# BoeBot-Schematic.net
KiCad netlist of a schematic drawn in EAGLE
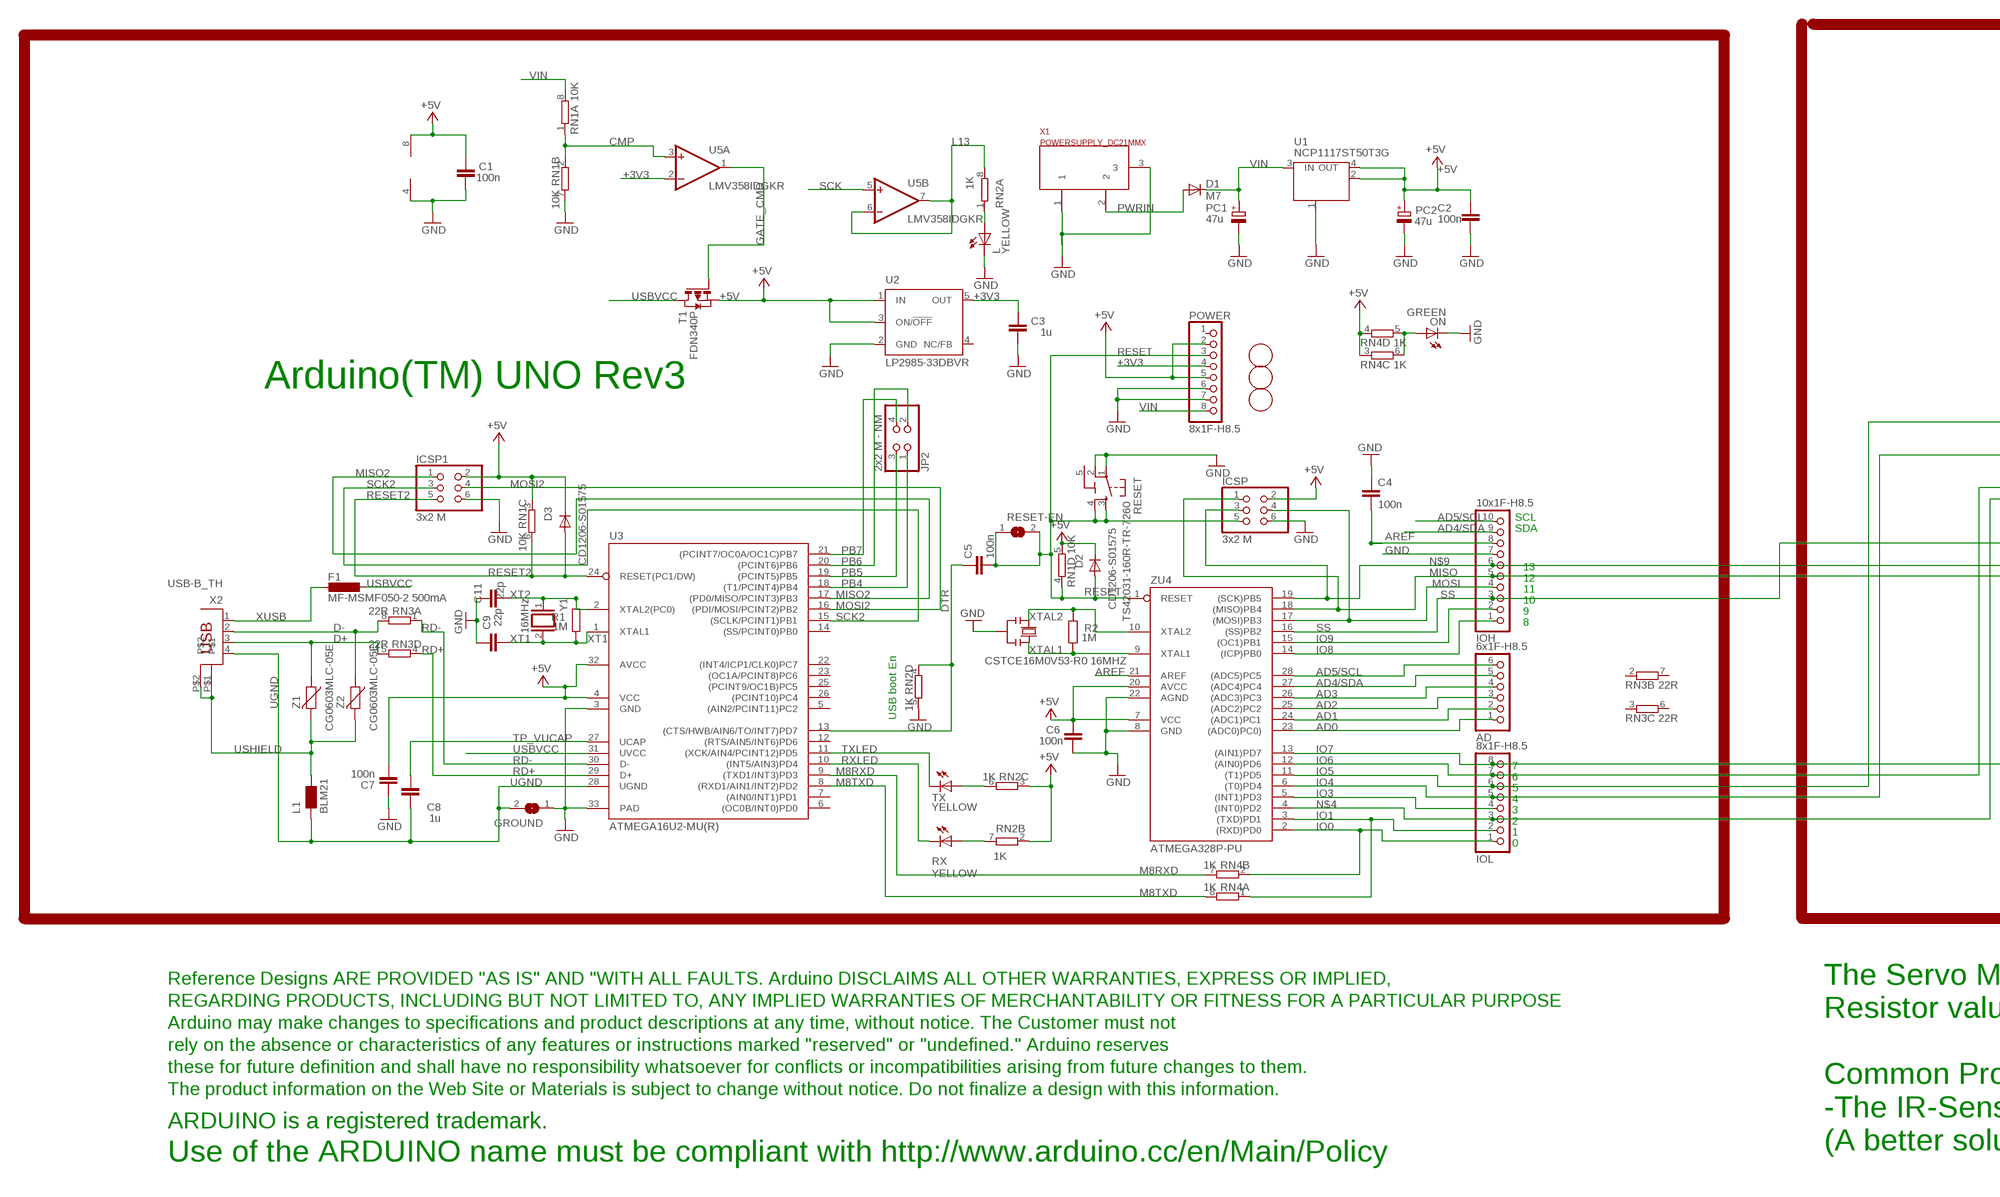
[diagram p0: schematic, sheet 1, part 1 of 2]
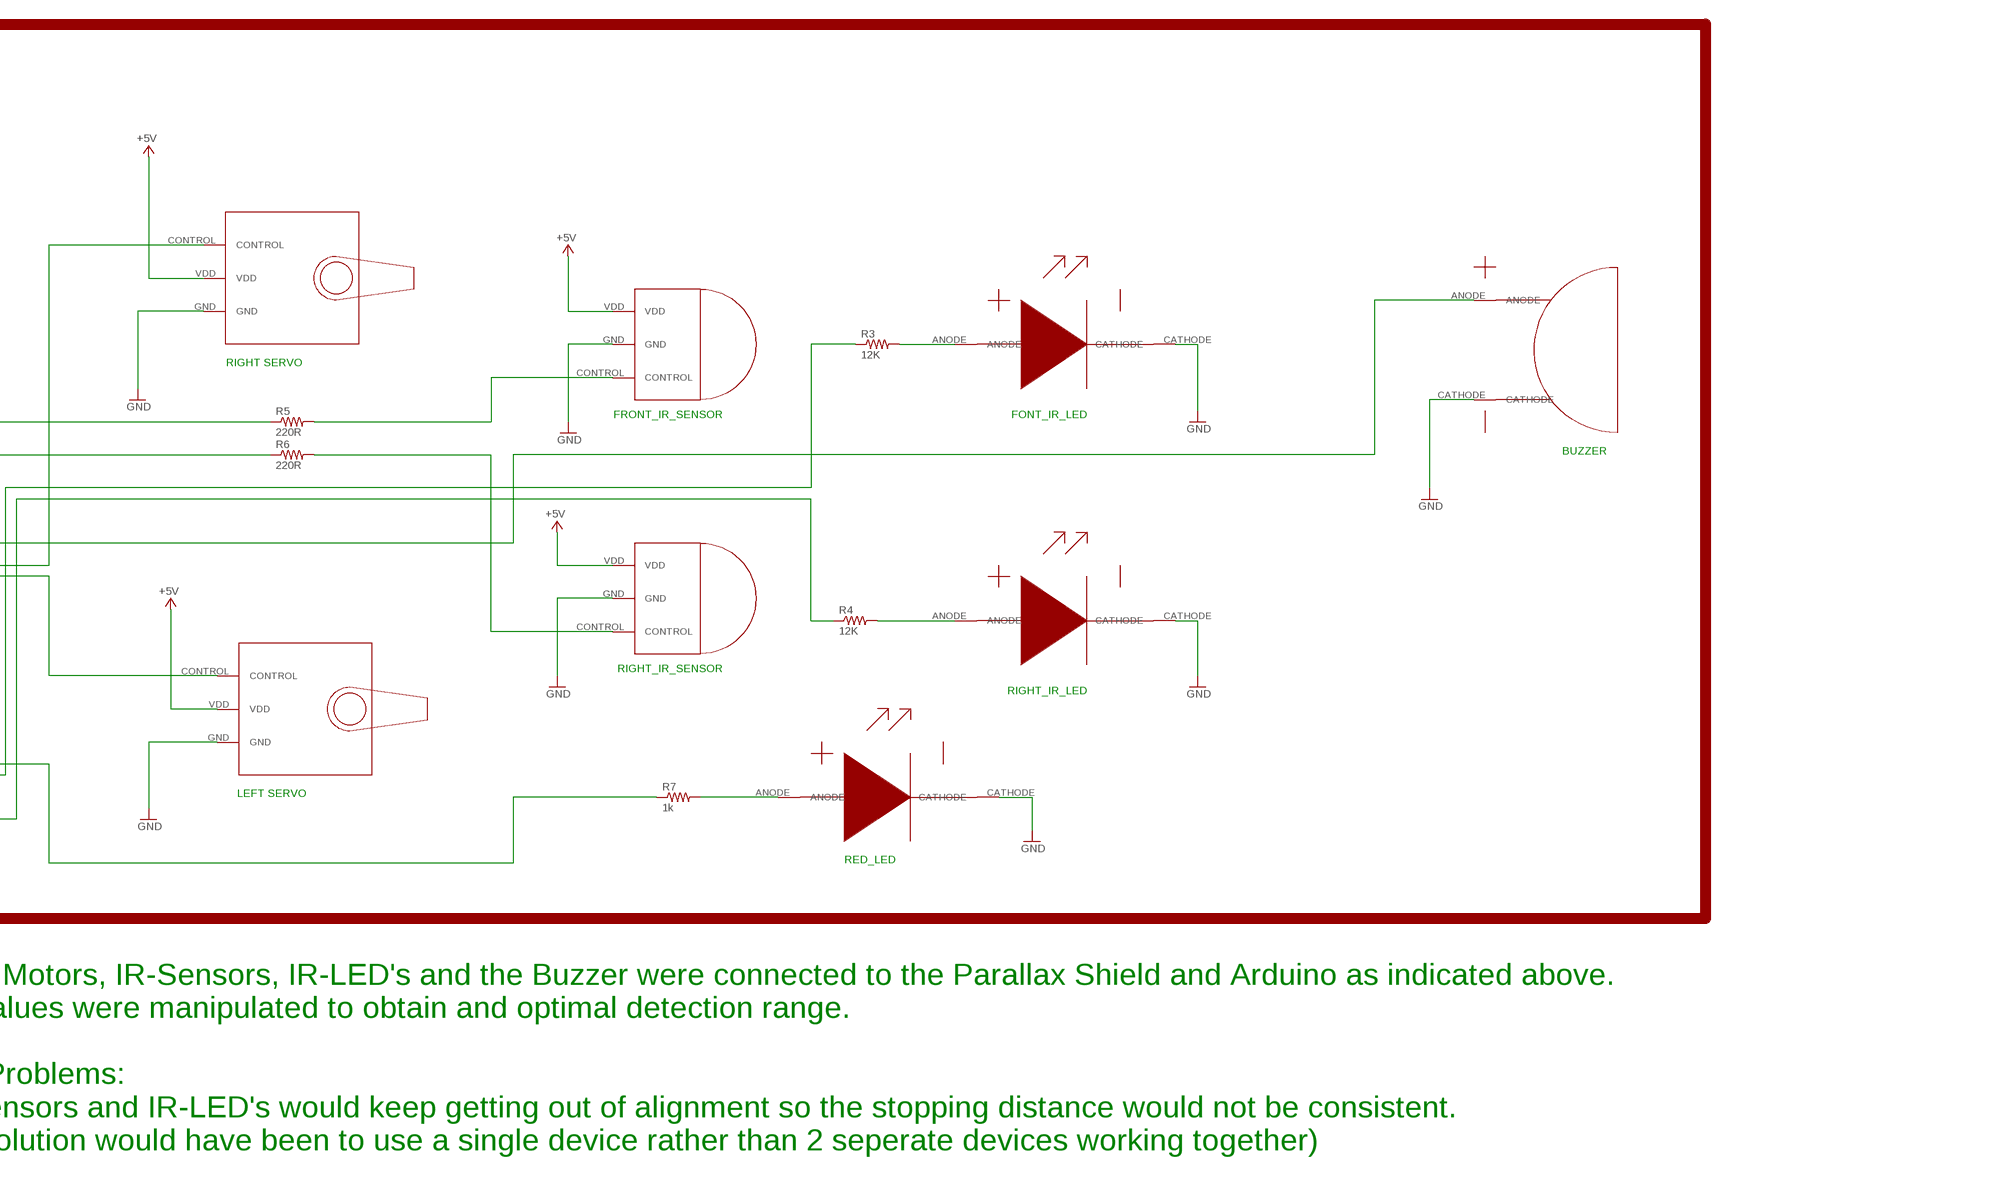
[diagram p1: schematic, sheet 1, part 2 of 2]

(export (version "E")
  (design (tool "Eeschema 10.0.6"))
  (components
    (comp (ref "AD")
      (value "6x1F-H8.5")
      (footprint "eagle-import:1X06")
      (libsource (lib "eagle-import") (part "PINHD-1X6"))
    )
    (comp (ref "C1")
      (value "100n")
      (footprint "eagle-import:C0603-ROUND")
      (libsource (lib "eagle-import") (part "C-EU0603-RND"))
    )
    (comp (ref "C2")
      (value "100n")
      (footprint "eagle-import:C0603-ROUND")
      (libsource (lib "eagle-import") (part "C-EU0603-RND"))
    )
    (comp (ref "C3")
      (value "1u")
      (footprint "eagle-import:C0603-ROUND")
      (libsource (lib "eagle-import") (part "C-EU0603-RND"))
    )
    (comp (ref "C4")
      (value "100n")
      (footprint "eagle-import:C0603-ROUND")
      (libsource (lib "eagle-import") (part "C-EU0603-RND"))
    )
    (comp (ref "C5")
      (value "100n")
      (footprint "eagle-import:C0603-ROUND")
      (libsource (lib "eagle-import") (part "C-EU0603-RND"))
    )
    (comp (ref "C6")
      (value "100n")
      (footprint "eagle-import:C0603-ROUND")
      (libsource (lib "eagle-import") (part "C-EU0603-RND"))
    )
    (comp (ref "C7")
      (value "100n")
      (footprint "eagle-import:C0603-ROUND")
      (libsource (lib "eagle-import") (part "C-EU0603-RND"))
    )
    (comp (ref "C8")
      (value "1u")
      (footprint "eagle-import:C0603-ROUND")
      (libsource (lib "eagle-import") (part "C-EU0603-RND"))
    )
    (comp (ref "C9")
      (value "22p")
      (footprint "eagle-import:C0603-ROUND")
      (libsource (lib "eagle-import") (part "C-EU0603-RND"))
    )
    (comp (ref "C11")
      (value "22p")
      (footprint "eagle-import:C0603-ROUND")
      (libsource (lib "eagle-import") (part "C-EU0603-RND"))
    )
    (comp (ref "D1")
      (value "M7")
      (footprint "eagle-import:SMB")
      (libsource (lib "eagle-import") (part "DIODE-SMB"))
    )
    (comp (ref "D2")
      (value "CD1206-S01575")
      (footprint "eagle-import:MINIMELF")
      (libsource (lib "eagle-import") (part "DIODE-MINIMELF"))
    )
    (comp (ref "D3")
      (value "CD1206-S01575")
      (footprint "eagle-import:MINIMELF")
      (libsource (lib "eagle-import") (part "DIODE-MINIMELF"))
    )
    (comp (ref "F1")
      (value "MF-MSMF050-2 500mA")
      (footprint "eagle-import:L1812")
      (libsource (lib "eagle-import") (part "L-EUL1812"))
    )
    (comp (ref "FD1")
      (value "FIDUCIALMOUNT")
      (footprint "eagle-import:FIDUCIA-MOUNT")
      (libsource (lib "eagle-import") (part "FIDUCIALMOUNT"))
    )
    (comp (ref "FD2")
      (value "FIDUCIALMOUNT")
      (footprint "eagle-import:FIDUCIA-MOUNT")
      (libsource (lib "eagle-import") (part "FIDUCIALMOUNT"))
    )
    (comp (ref "FD3")
      (value "FIDUCIALMOUNT")
      (footprint "eagle-import:FIDUCIA-MOUNT")
      (libsource (lib "eagle-import") (part "FIDUCIALMOUNT"))
    )
    (comp (ref "GROUND")
      (value "SJ")
      (footprint "eagle-import:SJ")
      (libsource (lib "eagle-import") (part "SJ"))
    )
    (comp (ref "ICSP")
      (value "3x2 M")
      (footprint "eagle-import:2X03")
      (libsource (lib "eagle-import") (part "PINHD-2X3"))
    )
    (comp (ref "ICSP1")
      (value "3x2 M")
      (footprint "eagle-import:2X03")
      (libsource (lib "eagle-import") (part "PINHD-2X3"))
    )
    (comp (ref "IOH")
      (value "10x1F-H8.5")
      (footprint "eagle-import:1X10")
      (libsource (lib "eagle-import") (part "PINHD-1X10_ARD"))
    )
    (comp (ref "IOL")
      (value "8x1F-H8.5")
      (footprint "eagle-import:1X08")
      (libsource (lib "eagle-import") (part "PINHD-1X8"))
    )
    (comp (ref "JP2")
      (value "2x2 M - NM")
      (footprint "eagle-import:2X02")
      (libsource (lib "eagle-import") (part "PINHD-2X2"))
    )
    (comp (ref "L")
      (value "YELLOW")
      (footprint "eagle-import:CHIP-LED0805")
      (libsource (lib "eagle-import") (part "LEDCHIP-LED0805"))
    )
    (comp (ref "L1")
      (value "BLM21")
      (footprint "eagle-import:0805")
      (libsource (lib "eagle-import") (part "WE-CBF_0805"))
    )
    (comp (ref "ON")
      (value "GREEN")
      (footprint "eagle-import:CHIP-LED0805")
      (libsource (lib "eagle-import") (part "LEDCHIP-LED0805"))
    )
    (comp (ref "PC1")
      (value "47u")
      (footprint "eagle-import:PANASONIC_D")
      (libsource (lib "eagle-import") (part "CPOL-EUD"))
    )
    (comp (ref "PC2")
      (value "47u")
      (footprint "eagle-import:PANASONIC_D")
      (libsource (lib "eagle-import") (part "CPOL-EUD"))
    )
    (comp (ref "POWER")
      (value "8x1F-H8.5")
      (footprint "eagle-import:1X08")
      (libsource (lib "eagle-import") (part "PINHD-1X8"))
    )
    (comp (ref "R1")
      (value "1M")
      (footprint "eagle-import:R0603-ROUND")
      (libsource (lib "eagle-import") (part "R-EU_R0603"))
    )
    (comp (ref "R2")
      (value "1M")
      (footprint "eagle-import:R0603-ROUND")
      (libsource (lib "eagle-import") (part "R-EU_R0603"))
    )
    (comp (ref "R3")
      (value "12K")
      (footprint "eagle-import:0411_15")
      (libsource (lib "eagle-import") (part "R-US_0411/15"))
    )
    (comp (ref "R4")
      (value "12K")
      (footprint "eagle-import:0411_15")
      (libsource (lib "eagle-import") (part "R-US_0411/15"))
    )
    (comp (ref "R5")
      (value "220R")
      (footprint "eagle-import:0207_2V")
      (libsource (lib "eagle-import") (part "R-US_0207/2V"))
    )
    (comp (ref "R6")
      (value "220R")
      (footprint "eagle-import:0207_2V")
      (libsource (lib "eagle-import") (part "R-US_0207/2V"))
    )
    (comp (ref "R7")
      (value "1k")
      (footprint "eagle-import:0207_2V")
      (libsource (lib "eagle-import") (part "R-US_0207/2V"))
    )
    (comp (ref "RESET")
      (value "TS42031-160R-TR-7260")
      (footprint "eagle-import:TS42")
      (libsource (lib "eagle-import") (part "TS42"))
    )
    (comp (ref "RESET-EN")
      (value "SJ")
      (footprint "eagle-import:SJ")
      (libsource (lib "eagle-import") (part "SJ"))
    )
    (comp (ref "RIGHT_IR_LED")
      (value "asdfa")
      (footprint "eagle-import:IR_SENSOR")
      (libsource (lib "eagle-import") (part "IR_SENSOR"))
    )
    (comp (ref "RIGHT_SERVO")
      (value "IR_LED")
      (footprint "eagle-import:IR_LED")
      (libsource (lib "eagle-import") (part "Servo_IR_LED"))
    )
    (comp (ref "RN1")
      (value "10K")
      (footprint "eagle-import:CAY16")
      (libsource (lib "eagle-import") (part "4R-NCAY16"))
    )
    (comp (ref "RN2")
      (value "1K")
      (footprint "eagle-import:CAY16")
      (libsource (lib "eagle-import") (part "4R-NCAY16"))
    )
    (comp (ref "RN3")
      (value "22R")
      (footprint "eagle-import:CAY16")
      (libsource (lib "eagle-import") (part "4R-NCAY16"))
    )
    (comp (ref "RN4")
      (value "1K")
      (footprint "eagle-import:CAY16")
      (libsource (lib "eagle-import") (part "4R-NCAY16"))
    )
    (comp (ref "RX")
      (value "YELLOW")
      (footprint "eagle-import:CHIP-LED0805")
      (libsource (lib "eagle-import") (part "LEDCHIP-LED0805"))
    )
    (comp (ref "T1")
      (value "FDN340P")
      (footprint "eagle-import:SOT-23")
      (libsource (lib "eagle-import") (part "PMOSSOT23"))
    )
    (comp (ref "TX")
      (value "YELLOW")
      (footprint "eagle-import:CHIP-LED0805")
      (libsource (lib "eagle-import") (part "LEDCHIP-LED0805"))
    )
    (comp (ref "U$1")
      (value "DISCLAIMER")
      (footprint "eagle-import:DISCLAIMER")
      (libsource (lib "eagle-import") (part "DISCLAIMER"))
    )
    (comp (ref "U$2")
      (value "BUZZER")
      (footprint "eagle-import:BUZZER")
      (libsource (lib "eagle-import") (part "BUZZER"))
    )
    (comp (ref "U$3")
      (value "IR_LED")
      (footprint "eagle-import:IR_LED")
      (libsource (lib "eagle-import") (part "Servo_IR_LED"))
    )
    (comp (ref "U$4")
      (value "IR_LED")
      (footprint "eagle-import:IR_LED")
      (libsource (lib "eagle-import") (part "IR_LED"))
    )
    (comp (ref "U$5")
      (value "IR_SENSOR")
      (footprint "eagle-import:IR_SENSOR")
      (libsource (lib "eagle-import") (part "IR_SENSOR"))
    )
    (comp (ref "U$6")
      (value "IR_LED")
      (footprint "eagle-import:IR_LED")
      (libsource (lib "eagle-import") (part "IR_LED"))
    )
    (comp (ref "U$7")
      (value "IR_LED")
      (footprint "eagle-import:IR_LED")
      (libsource (lib "eagle-import") (part "IR_LED"))
    )
    (comp (ref "U1")
      (value "NCP1117ST50T3G")
      (footprint "eagle-import:SOT223")
      (libsource (lib "eagle-import") (part "MC33269ST-3.3T3"))
    )
    (comp (ref "U2")
      (value "LP2985-33DBVR")
      (footprint "eagle-import:SOT23-DBV")
      (libsource (lib "eagle-import") (part "LP2985-XXDBVR33"))
    )
    (comp (ref "U3")
      (value "ATMEGA16U2-MU(R)")
      (footprint "eagle-import:MLF32")
      (libsource (lib "eagle-import") (part "ATMEGA16U2-MU"))
    )
    (comp (ref "U5")
      (value "LMV358IDGKR")
      (footprint "eagle-import:MSOP08")
      (libsource (lib "eagle-import") (part "LMV358?MMX"))
    )
    (comp (ref "X1")
      (value "POWERSUPPLY_DC21MMX")
      (footprint "eagle-import:POWERSUPPLY_DC-21MM")
      (libsource (lib "eagle-import") (part "POWERSUPPLY_DC21MMX"))
    )
    (comp (ref "X2")
      (value "USB-B_TH")
      (footprint "eagle-import:PN61729")
      (libsource (lib "eagle-import") (part "PN61729"))
    )
    (comp (ref "Y1")
      (value "16MHz")
      (footprint "eagle-import:QS")
      (libsource (lib "eagle-import") (part "XTAL/S"))
    )
    (comp (ref "Y2")
      (value "CSTCE16M0V53-R0 16MHZ")
      (footprint "eagle-import:RESONATOR")
      (libsource (lib "eagle-import") (part "RESONATORMU"))
    )
    (comp (ref "Z1")
      (value "CG0603MLC-05E")
      (footprint "eagle-import:CT_CN0603")
      (libsource (lib "eagle-import") (part "VARISTORCN0603"))
    )
    (comp (ref "Z2")
      (value "CG0603MLC-05E")
      (footprint "eagle-import:CT_CN0603")
      (libsource (lib "eagle-import") (part "VARISTORCN0603"))
    )
    (comp (ref "ZU4")
      (value "ATMEGA328P-PU")
      (footprint "eagle-import:DIL28-3")
      (libsource (lib "eagle-import") (part "ATMEGA328P-PU"))
    )
  )
  (nets
    (net (code "1") (name "+5V") (class "Default")
      (node (ref "C1") (pin "2") (pinfunction "2_2") (pintype "passive"))
      (node (ref "C2") (pin "2") (pinfunction "2_2") (pintype "passive"))
      (node (ref "C6") (pin "2") (pinfunction "2_2") (pintype "passive"))
      (node (ref "C7") (pin "1") (pinfunction "1_1") (pintype "passive"))
      (node (ref "D2") (pin "C") (pinfunction "C_C") (pintype "passive"))
      (node (ref "D3") (pin "C") (pinfunction "C_C") (pintype "passive"))
      (node (ref "ICSP") (pin "2") (pinfunction "2_2") (pintype "passive"))
      (node (ref "ICSP1") (pin "2") (pinfunction "2_2") (pintype "passive"))
      (node (ref "PC2") (pin "+") (pinfunction "+_+") (pintype "passive"))
      (node (ref "POWER") (pin "2") (pinfunction "2_2") (pintype "passive"))
      (node (ref "POWER") (pin "5") (pinfunction "5_5") (pintype "passive"))
      (node (ref "RIGHT_IR_LED") (pin "VDD") (pinfunction "VDD_VDD") (pintype "bidirectional"))
      (node (ref "RIGHT_SERVO") (pin "VDD") (pinfunction "VDD_VDD") (pintype "bidirectional"))
      (node (ref "RN1") (pin "3") (pinfunction "1_3") (pintype "passive"))
      (node (ref "RN1") (pin "5") (pinfunction "2_5") (pintype "passive"))
      (node (ref "RN2") (pin "2") (pinfunction "1_2") (pintype "passive"))
      (node (ref "RN2") (pin "3") (pinfunction "1_3") (pintype "passive"))
      (node (ref "RN4") (pin "3") (pinfunction "1_3") (pintype "passive"))
      (node (ref "RN4") (pin "4") (pinfunction "1_4") (pintype "passive"))
      (node (ref "T1") (pin "2") (pinfunction "S_2") (pintype "passive"))
      (node (ref "U$3") (pin "VDD") (pinfunction "VDD_VDD") (pintype "bidirectional"))
      (node (ref "U$5") (pin "VDD") (pinfunction "VDD_VDD") (pintype "bidirectional"))
      (node (ref "U1") (pin "2") (pinfunction "OUT_2") (pintype "passive"))
      (node (ref "U1") (pin "4") (pinfunction "OUT_4") (pintype "passive"))
      (node (ref "U2") (pin "1") (pinfunction "IN_1") (pintype "input"))
      (node (ref "U2") (pin "3") (pinfunction "ON/~{OFF}_3") (pintype "input"))
      (node (ref "U3") (pin "32") (pinfunction "AVCC_32") (pintype "power_in"))
      (node (ref "U3") (pin "4") (pinfunction "VCC_4") (pintype "power_in"))
      (node (ref "U5") (pin "8") (pinfunction "V+_8") (pintype "power_in"))
      (node (ref "ZU4") (pin "20") (pinfunction "AVCC_20") (pintype "power_in"))
      (node (ref "ZU4") (pin "7") (pinfunction "VCC_7") (pintype "power_in"))
    )
    (net (code "2") (name "/+3V3") (class "Default")
      (node (ref "C3") (pin "2") (pinfunction "2_2") (pintype "passive"))
      (node (ref "POWER") (pin "4") (pinfunction "4_4") (pintype "passive"))
      (node (ref "U2") (pin "5") (pinfunction "OUT_5") (pintype "passive"))
      (node (ref "U5") (pin "2") (pinfunction "-IN_2") (pintype "input"))
    )
    (net (code "3") (name "/5-GND") (class "Default")
      (node (ref "RESET") (pin "5") (pinfunction "5-GND_5") (pintype "power_in"))
    )
    (net (code "4") (name "/AD0") (class "Default")
      (node (ref "AD") (pin "1") (pinfunction "1_1") (pintype "passive"))
      (node (ref "ZU4") (pin "23") (pinfunction "(ADC0)PC0)_23") (pintype "bidirectional"))
    )
    (net (code "5") (name "/AD1") (class "Default")
      (node (ref "AD") (pin "2") (pinfunction "2_2") (pintype "passive"))
      (node (ref "ZU4") (pin "24") (pinfunction "(ADC1)PC1_24") (pintype "bidirectional"))
    )
    (net (code "6") (name "/AD2") (class "Default")
      (node (ref "AD") (pin "3") (pinfunction "3_3") (pintype "passive"))
      (node (ref "ZU4") (pin "25") (pinfunction "(ADC2)PC2_25") (pintype "bidirectional"))
    )
    (net (code "7") (name "/AD3") (class "Default")
      (node (ref "AD") (pin "4") (pinfunction "4_4") (pintype "passive"))
      (node (ref "ZU4") (pin "26") (pinfunction "(ADC3)PC3_26") (pintype "bidirectional"))
    )
    (net (code "8") (name "/AD4{slash}SDA") (class "Default")
      (node (ref "AD") (pin "5") (pinfunction "5_5") (pintype "passive"))
      (node (ref "IOH") (pin "9") (pinfunction "9_9") (pintype "passive"))
      (node (ref "ZU4") (pin "27") (pinfunction "(ADC4)PC4_27") (pintype "bidirectional"))
    )
    (net (code "9") (name "/AD5{slash}SCL") (class "Default")
      (node (ref "AD") (pin "6") (pinfunction "6_6") (pintype "passive"))
      (node (ref "IOH") (pin "10") (pinfunction "10_10") (pintype "passive"))
      (node (ref "ZU4") (pin "28") (pinfunction "(ADC5)PC5_28") (pintype "bidirectional"))
    )
    (net (code "10") (name "/AREF") (class "Default")
      (node (ref "C4") (pin "2") (pinfunction "2_2") (pintype "passive"))
      (node (ref "IOH") (pin "8") (pinfunction "8_8") (pintype "passive"))
      (node (ref "ZU4") (pin "21") (pinfunction "AREF_21") (pintype "passive"))
    )
    (net (code "11") (name "/CMP") (class "Default")
      (node (ref "RN1") (pin "1") (pinfunction "1_1") (pintype "passive"))
      (node (ref "RN1") (pin "2") (pinfunction "1_2") (pintype "passive"))
      (node (ref "U5") (pin "3") (pinfunction "+IN_3") (pintype "input"))
    )
    (net (code "12") (name "/D+") (class "Default")
      (node (ref "RN3") (pin "5") (pinfunction "2_5") (pintype "passive"))
      (node (ref "X2") (pin "3") (pinfunction "3_3") (pintype "bidirectional"))
      (node (ref "Z1") (pin "1") (pinfunction "1_1") (pintype "passive"))
    )
    (net (code "13") (name "/D-") (class "Default")
      (node (ref "RN3") (pin "8") (pinfunction "2_8") (pintype "passive"))
      (node (ref "X2") (pin "2") (pinfunction "2_2") (pintype "bidirectional"))
      (node (ref "Z2") (pin "1") (pinfunction "1_1") (pintype "passive"))
    )
    (net (code "14") (name "/DTR") (class "Default")
      (node (ref "C5") (pin "1") (pinfunction "1_1") (pintype "passive"))
      (node (ref "RN2") (pin "4") (pinfunction "1_4") (pintype "passive"))
      (node (ref "U3") (pin "13") (pinfunction "(CTS/HWB/AIN6/TO/INT7)PD7_13") (pintype "bidirectional"))
    )
    (net (code "15") (name "/GATE_CMD") (class "Default")
      (node (ref "T1") (pin "3") (pinfunction "G_3") (pintype "passive"))
      (node (ref "U5") (pin "1") (pinfunction "OUT_1") (pintype "output"))
    )
    (net (code "16") (name "/IO0") (class "Default")
      (node (ref "IOL") (pin "1") (pinfunction "1_1") (pintype "passive"))
      (node (ref "RN4") (pin "2") (pinfunction "1_2") (pintype "passive"))
      (node (ref "ZU4") (pin "2") (pinfunction "(RXD)PD0_2") (pintype "bidirectional"))
    )
    (net (code "17") (name "/IO1") (class "Default")
      (node (ref "IOL") (pin "2") (pinfunction "2_2") (pintype "passive"))
      (node (ref "RN4") (pin "1") (pinfunction "1_1") (pintype "passive"))
      (node (ref "ZU4") (pin "3") (pinfunction "(TXD)PD1_3") (pintype "bidirectional"))
    )
    (net (code "18") (name "/IO3") (class "Default")
      (node (ref "IOL") (pin "4") (pinfunction "4_4") (pintype "passive"))
      (node (ref "ZU4") (pin "5") (pinfunction "(INT1)PD3_5") (pintype "bidirectional"))
    )
    (net (code "19") (name "/IO4") (class "Default")
      (node (ref "IOL") (pin "5") (pinfunction "5_5") (pintype "passive"))
      (node (ref "R6") (pin "1") (pinfunction "1_1") (pintype "passive"))
      (node (ref "ZU4") (pin "6") (pinfunction "(T0)PD4_6") (pintype "bidirectional"))
    )
    (net (code "20") (name "/IO5") (class "Default")
      (node (ref "IOL") (pin "6") (pinfunction "6_6") (pintype "passive"))
      (node (ref "R5") (pin "1") (pinfunction "1_1") (pintype "passive"))
      (node (ref "ZU4") (pin "11") (pinfunction "(T1)PD5_11") (pintype "bidirectional"))
    )
    (net (code "21") (name "/IO6") (class "Default")
      (node (ref "IOL") (pin "7") (pinfunction "7_7") (pintype "passive"))
      (node (ref "R3") (pin "1") (pinfunction "1_1") (pintype "passive"))
      (node (ref "ZU4") (pin "12") (pinfunction "(AIN0)PD6_12") (pintype "bidirectional"))
    )
    (net (code "22") (name "/IO7") (class "Default")
      (node (ref "IOL") (pin "8") (pinfunction "8_8") (pintype "passive"))
      (node (ref "R7") (pin "1") (pinfunction "1_1") (pintype "passive"))
      (node (ref "ZU4") (pin "13") (pinfunction "(AIN1)PD7_13") (pintype "bidirectional"))
    )
    (net (code "23") (name "/IO8") (class "Default")
      (node (ref "IOH") (pin "1") (pinfunction "1_1") (pintype "passive"))
      (node (ref "ZU4") (pin "14") (pinfunction "(ICP)PB0_14") (pintype "bidirectional"))
    )
    (net (code "24") (name "/IO9") (class "Default")
      (node (ref "IOH") (pin "2") (pinfunction "2_2") (pintype "passive"))
      (node (ref "ZU4") (pin "15") (pinfunction "(OC1)PB1_15") (pintype "bidirectional"))
    )
    (net (code "25") (name "/L13") (class "Default")
      (node (ref "RN2") (pin "8") (pinfunction "2_8") (pintype "passive"))
      (node (ref "U5") (pin "6") (pinfunction "-IN_6") (pintype "input"))
      (node (ref "U5") (pin "7") (pinfunction "OUT_7") (pintype "output"))
    )
    (net (code "26") (name "/M8RXD") (class "Default")
      (node (ref "RN4") (pin "7") (pinfunction "2_7") (pintype "passive"))
      (node (ref "U3") (pin "9") (pinfunction "(TXD1/INT3)PD3_9") (pintype "bidirectional"))
    )
    (net (code "27") (name "/M8TXD") (class "Default")
      (node (ref "RN4") (pin "8") (pinfunction "2_8") (pintype "passive"))
      (node (ref "U3") (pin "8") (pinfunction "(RXD1/AIN1/INT2)PD2_8") (pintype "bidirectional"))
    )
    (net (code "28") (name "/MISO") (class "Default")
      (node (ref "ICSP") (pin "1") (pinfunction "1_1") (pintype "passive"))
      (node (ref "IOH") (pin "5") (pinfunction "5_5") (pintype "passive"))
      (node (ref "U$3") (pin "CONTROL") (pinfunction "CONTROL_CONTROL") (pintype "bidirectional"))
      (node (ref "ZU4") (pin "18") (pinfunction "(MISO)PB4_18") (pintype "bidirectional"))
    )
    (net (code "29") (name "/MISO2") (class "Default")
      (node (ref "ICSP1") (pin "1") (pinfunction "1_1") (pintype "passive"))
      (node (ref "U3") (pin "17") (pinfunction "(PD0/MISO/PCINT3)PB3_17") (pintype "bidirectional"))
    )
    (net (code "30") (name "/MOSI") (class "Default")
      (node (ref "ICSP") (pin "4") (pinfunction "4_4") (pintype "passive"))
      (node (ref "IOH") (pin "4") (pinfunction "4_4") (pintype "passive"))
      (node (ref "ZU4") (pin "17") (pinfunction "(MOSI)PB3_17") (pintype "bidirectional"))
    )
    (net (code "31") (name "/MOSI2") (class "Default")
      (node (ref "ICSP1") (pin "4") (pinfunction "4_4") (pintype "passive"))
      (node (ref "U3") (pin "16") (pinfunction "(PDI/MOSI/PCINT2)PB2_16") (pintype "bidirectional"))
    )
    (net (code "32") (name "/N$4") (class "Default")
      (node (ref "IOL") (pin "3") (pinfunction "3_3") (pintype "passive"))
      (node (ref "R4") (pin "1") (pinfunction "1_1") (pintype "passive"))
      (node (ref "ZU4") (pin "4") (pinfunction "(INT0)PD2_4") (pintype "bidirectional"))
    )
    (net (code "33") (name "/N$9") (class "Default")
      (node (ref "ICSP") (pin "3") (pinfunction "3_3") (pintype "passive"))
      (node (ref "IOH") (pin "6") (pinfunction "6_6") (pintype "passive"))
      (node (ref "RIGHT_SERVO") (pin "CONTROL") (pinfunction "CONTROL_CONTROL") (pintype "bidirectional"))
      (node (ref "ZU4") (pin "19") (pinfunction "(SCK)PB5_19") (pintype "bidirectional"))
    )
    (net (code "34") (name "/PB4") (class "Default")
      (node (ref "JP2") (pin "1") (pinfunction "1_1") (pintype "passive"))
      (node (ref "U3") (pin "18") (pinfunction "(T1/PCINT4)PB4_18") (pintype "bidirectional"))
    )
    (net (code "35") (name "/PB5") (class "Default")
      (node (ref "JP2") (pin "3") (pinfunction "3_3") (pintype "passive"))
      (node (ref "U3") (pin "19") (pinfunction "(PCINT5)PB5_19") (pintype "bidirectional"))
    )
    (net (code "36") (name "/PB6") (class "Default")
      (node (ref "JP2") (pin "2") (pinfunction "2_2") (pintype "passive"))
      (node (ref "U3") (pin "20") (pinfunction "(PCINT6)PB6_20") (pintype "bidirectional"))
    )
    (net (code "37") (name "/PB7") (class "Default")
      (node (ref "JP2") (pin "4") (pinfunction "4_4") (pintype "passive"))
      (node (ref "U3") (pin "21") (pinfunction "(PCINT7/OC0A/OC1C)PB7_21") (pintype "bidirectional"))
    )
    (net (code "38") (name "/PWRIN") (class "Default")
      (node (ref "D1") (pin "A") (pinfunction "A_A") (pintype "passive"))
      (node (ref "X1") (pin "2") (pinfunction "2_2") (pintype "power_in"))
    )
    (net (code "39") (name "/RD+") (class "Default")
      (node (ref "RN3") (pin "4") (pinfunction "1_4") (pintype "passive"))
      (node (ref "U3") (pin "29") (pinfunction "D+_29") (pintype "bidirectional"))
    )
    (net (code "40") (name "/RD-") (class "Default")
      (node (ref "RN3") (pin "1") (pinfunction "1_1") (pintype "passive"))
      (node (ref "U3") (pin "30") (pinfunction "D-_30") (pintype "bidirectional"))
    )
    (net (code "41") (name "/RESET") (class "Default")
      (node (ref "C5") (pin "2") (pinfunction "2_2") (pintype "passive"))
      (node (ref "D2") (pin "A") (pinfunction "A_A") (pintype "passive"))
      (node (ref "ICSP") (pin "5") (pinfunction "5_5") (pintype "passive"))
      (node (ref "POWER") (pin "3") (pinfunction "3_3") (pintype "passive"))
      (node (ref "RESET") (pin "3") (pinfunction "3_3") (pintype "passive"))
      (node (ref "RESET") (pin "4") (pinfunction "4_4") (pintype "passive"))
      (node (ref "RESET-EN") (pin "1") (pinfunction "1_1") (pintype "passive"))
      (node (ref "RESET-EN") (pin "2") (pinfunction "2_2") (pintype "passive"))
      (node (ref "RN1") (pin "4") (pinfunction "1_4") (pintype "passive"))
      (node (ref "ZU4") (pin "1") (pinfunction "RESET_1") (pintype "input"))
    )
    (net (code "42") (name "/RESET2") (class "Default")
      (node (ref "D3") (pin "A") (pinfunction "A_A") (pintype "passive"))
      (node (ref "ICSP1") (pin "5") (pinfunction "5_5") (pintype "passive"))
      (node (ref "RN1") (pin "6") (pinfunction "2_6") (pintype "passive"))
      (node (ref "U3") (pin "24") (pinfunction "RESET(PC1/DW)_24") (pintype "input"))
    )
    (net (code "43") (name "/RXLED") (class "Default")
      (node (ref "RX") (pin "C") (pinfunction "C_C") (pintype "passive"))
      (node (ref "U3") (pin "10") (pinfunction "(INT5/AIN3)PD4_10") (pintype "bidirectional"))
    )
    (net (code "44") (name "/SCK") (class "Default")
      (node (ref "U5") (pin "5") (pinfunction "+IN_5") (pintype "input"))
    )
    (net (code "45") (name "/SCK2") (class "Default")
      (node (ref "ICSP1") (pin "3") (pinfunction "3_3") (pintype "passive"))
      (node (ref "U3") (pin "15") (pinfunction "(SCLK/PCINT1)PB1_15") (pintype "bidirectional"))
    )
    (net (code "46") (name "/SS") (class "Default")
      (node (ref "IOH") (pin "3") (pinfunction "3_3") (pintype "passive"))
      (node (ref "U$2") (pin "ANODE") (pinfunction "ANODE_ANODE") (pintype "bidirectional"))
      (node (ref "ZU4") (pin "16") (pinfunction "(SS)PB2_16") (pintype "bidirectional"))
    )
    (net (code "47") (name "/TP_VUCAP") (class "Default")
      (node (ref "C8") (pin "1") (pinfunction "1_1") (pintype "passive"))
      (node (ref "U3") (pin "27") (pinfunction "UCAP_27") (pintype "passive"))
    )
    (net (code "48") (name "/TXLED") (class "Default")
      (node (ref "TX") (pin "C") (pinfunction "C_C") (pintype "passive"))
      (node (ref "U3") (pin "11") (pinfunction "(XCK/AIN4/PCINT12)PD5_11") (pintype "bidirectional"))
    )
    (net (code "49") (name "/UGND") (class "Default")
      (node (ref "C8") (pin "2") (pinfunction "2_2") (pintype "passive"))
      (node (ref "GROUND") (pin "2") (pinfunction "2_2") (pintype "passive"))
      (node (ref "L1") (pin "1") (pinfunction "1_1") (pintype "passive"))
      (node (ref "U3") (pin "28") (pinfunction "UGND_28") (pintype "power_in"))
      (node (ref "X2") (pin "4") (pinfunction "4_4") (pintype "bidirectional"))
    )
    (net (code "50") (name "/USBVCC") (class "Default")
      (node (ref "F1") (pin "1") (pinfunction "1_1") (pintype "passive"))
      (node (ref "T1") (pin "1") (pinfunction "D_1") (pintype "passive"))
      (node (ref "U3") (pin "31") (pinfunction "UVCC_31") (pintype "power_in"))
    )
    (net (code "51") (name "/USHIELD") (class "Default")
      (node (ref "L1") (pin "2") (pinfunction "2_2") (pintype "passive"))
      (node (ref "X2") (pin "P$1") (pinfunction "P$1_P$1") (pintype "bidirectional"))
      (node (ref "X2") (pin "P$2") (pinfunction "P$2_P$2") (pintype "bidirectional"))
      (node (ref "Z1") (pin "2") (pinfunction "2_2") (pintype "passive"))
      (node (ref "Z2") (pin "2") (pinfunction "2_2") (pintype "passive"))
    )
    (net (code "52") (name "/VIN") (class "Default")
      (node (ref "D1") (pin "C") (pinfunction "C_C") (pintype "passive"))
      (node (ref "PC1") (pin "+") (pinfunction "+_+") (pintype "passive"))
      (node (ref "POWER") (pin "8") (pinfunction "8_8") (pintype "passive"))
      (node (ref "RN1") (pin "8") (pinfunction "2_8") (pintype "passive"))
      (node (ref "U1") (pin "3") (pinfunction "IN_3") (pintype "input"))
    )
    (net (code "53") (name "/XT1") (class "Default")
      (node (ref "C9") (pin "1") (pinfunction "1_1") (pintype "passive"))
      (node (ref "R1") (pin "1") (pinfunction "1_1") (pintype "passive"))
      (node (ref "U3") (pin "1") (pinfunction "XTAL1_1") (pintype "bidirectional"))
      (node (ref "Y1") (pin "2") (pinfunction "2_2") (pintype "passive"))
    )
    (net (code "54") (name "/XT2") (class "Default")
      (node (ref "C11") (pin "1") (pinfunction "1_1") (pintype "passive"))
      (node (ref "R1") (pin "2") (pinfunction "2_2") (pintype "passive"))
      (node (ref "U3") (pin "2") (pinfunction "XTAL2(PC0)_2") (pintype "bidirectional"))
      (node (ref "Y1") (pin "1") (pinfunction "1_1") (pintype "passive"))
    )
    (net (code "55") (name "/XTAL1") (class "Default")
      (node (ref "R2") (pin "1") (pinfunction "1_1") (pintype "passive"))
      (node (ref "Y2") (pin "3") (pinfunction "3_3") (pintype "passive"))
      (node (ref "ZU4") (pin "9") (pinfunction "XTAL1_9") (pintype "bidirectional"))
    )
    (net (code "56") (name "/XTAL2") (class "Default")
      (node (ref "R2") (pin "2") (pinfunction "2_2") (pintype "passive"))
      (node (ref "Y2") (pin "1") (pinfunction "1_1") (pintype "passive"))
      (node (ref "ZU4") (pin "10") (pinfunction "XTAL2_10") (pintype "bidirectional"))
    )
    (net (code "57") (name "/XUSB") (class "Default")
      (node (ref "F1") (pin "2") (pinfunction "2_2") (pintype "passive"))
      (node (ref "X2") (pin "1") (pinfunction "1_1") (pintype "bidirectional"))
    )
    (net (code "58") (name "GND") (class "Default")
      (node (ref "C1") (pin "1") (pinfunction "1_1") (pintype "passive"))
      (node (ref "C11") (pin "2") (pinfunction "2_2") (pintype "passive"))
      (node (ref "C2") (pin "1") (pinfunction "1_1") (pintype "passive"))
      (node (ref "C3") (pin "1") (pinfunction "1_1") (pintype "passive"))
      (node (ref "C4") (pin "1") (pinfunction "1_1") (pintype "passive"))
      (node (ref "C6") (pin "1") (pinfunction "1_1") (pintype "passive"))
      (node (ref "C7") (pin "2") (pinfunction "2_2") (pintype "passive"))
      (node (ref "C9") (pin "2") (pinfunction "2_2") (pintype "passive"))
      (node (ref "GROUND") (pin "1") (pinfunction "1_1") (pintype "passive"))
      (node (ref "ICSP") (pin "6") (pinfunction "6_6") (pintype "passive"))
      (node (ref "ICSP1") (pin "6") (pinfunction "6_6") (pintype "passive"))
      (node (ref "IOH") (pin "7") (pinfunction "7_7") (pintype "passive"))
      (node (ref "L") (pin "C") (pinfunction "C_C") (pintype "passive"))
      (node (ref "ON") (pin "C") (pinfunction "C_C") (pintype "passive"))
      (node (ref "PC1") (pin "-") (pinfunction "-_-") (pintype "passive"))
      (node (ref "PC2") (pin "-") (pinfunction "-_-") (pintype "passive"))
      (node (ref "POWER") (pin "6") (pinfunction "6_6") (pintype "passive"))
      (node (ref "POWER") (pin "7") (pinfunction "7_7") (pintype "passive"))
      (node (ref "RESET") (pin "1") (pinfunction "1_1") (pintype "passive"))
      (node (ref "RESET") (pin "2") (pinfunction "2_2") (pintype "passive"))
      (node (ref "RIGHT_IR_LED") (pin "GND") (pinfunction "GND_GND") (pintype "bidirectional"))
      (node (ref "RIGHT_SERVO") (pin "GND") (pinfunction "GND_GND") (pintype "bidirectional"))
      (node (ref "RN1") (pin "7") (pinfunction "2_7") (pintype "passive"))
      (node (ref "RN2") (pin "5") (pinfunction "2_5") (pintype "passive"))
      (node (ref "U$2") (pin "CATHODE") (pinfunction "CATHODE_CATHODE") (pintype "bidirectional"))
      (node (ref "U$3") (pin "GND") (pinfunction "GND_GND") (pintype "bidirectional"))
      (node (ref "U$4") (pin "CATHODE") (pinfunction "CATHODE_CATHODE") (pintype "bidirectional"))
      (node (ref "U$5") (pin "GND") (pinfunction "GND_GND") (pintype "bidirectional"))
      (node (ref "U$6") (pin "CATHODE") (pinfunction "CATHODE_CATHODE") (pintype "bidirectional"))
      (node (ref "U$7") (pin "CATHODE") (pinfunction "CATHODE_CATHODE") (pintype "bidirectional"))
      (node (ref "U1") (pin "1") (pinfunction "GND/ADJ_1") (pintype "input"))
      (node (ref "U2") (pin "2") (pinfunction "GND_2") (pintype "power_in"))
      (node (ref "U3") (pin "3") (pinfunction "GND_3") (pintype "power_in"))
      (node (ref "U3") (pin "33") (pinfunction "PAD_33") (pintype "power_in"))
      (node (ref "U5") (pin "4") (pinfunction "V-_4") (pintype "power_in"))
      (node (ref "X1") (pin "1") (pinfunction "1_1") (pintype "power_in"))
      (node (ref "X1") (pin "3") (pinfunction "3_3") (pintype "power_in"))
      (node (ref "Y2") (pin "2") (pinfunction "2_2") (pintype "passive"))
      (node (ref "ZU4") (pin "22") (pinfunction "AGND_22") (pintype "power_in"))
      (node (ref "ZU4") (pin "8") (pinfunction "GND_8") (pintype "power_in"))
    )
    (net (code "59") (name "Net-(L-PadA)") (class "Default")
      (node (ref "L") (pin "A") (pinfunction "A_A") (pintype "passive"))
      (node (ref "RN2") (pin "1") (pinfunction "1_1") (pintype "passive"))
    )
    (net (code "60") (name "Net-(R3-Pad2)") (class "Default")
      (node (ref "R3") (pin "2") (pinfunction "2_2") (pintype "passive"))
      (node (ref "U$6") (pin "ANODE") (pinfunction "ANODE_ANODE") (pintype "bidirectional"))
    )
    (net (code "61") (name "Net-(R4-Pad2)") (class "Default")
      (node (ref "R4") (pin "2") (pinfunction "2_2") (pintype "passive"))
      (node (ref "U$7") (pin "ANODE") (pinfunction "ANODE_ANODE") (pintype "bidirectional"))
    )
    (net (code "62") (name "Net-(R5-Pad2)") (class "Default")
      (node (ref "R5") (pin "2") (pinfunction "2_2") (pintype "passive"))
      (node (ref "RIGHT_IR_LED") (pin "CONTROL") (pinfunction "CONTROL_CONTROL") (pintype "bidirectional"))
    )
    (net (code "63") (name "Net-(R6-Pad2)") (class "Default")
      (node (ref "R6") (pin "2") (pinfunction "2_2") (pintype "passive"))
      (node (ref "U$5") (pin "CONTROL") (pinfunction "CONTROL_CONTROL") (pintype "bidirectional"))
    )
    (net (code "64") (name "Net-(R7-Pad2)") (class "Default")
      (node (ref "R7") (pin "2") (pinfunction "2_2") (pintype "passive"))
      (node (ref "U$4") (pin "ANODE") (pinfunction "ANODE_ANODE") (pintype "bidirectional"))
    )
    (net (code "65") (name "Net-(RN2B-2)") (class "Default")
      (node (ref "RN2") (pin "7") (pinfunction "2_7") (pintype "passive"))
      (node (ref "RX") (pin "A") (pinfunction "A_A") (pintype "passive"))
    )
    (net (code "66") (name "Net-(RN2C-2)") (class "Default")
      (node (ref "RN2") (pin "6") (pinfunction "2_6") (pintype "passive"))
      (node (ref "TX") (pin "A") (pinfunction "A_A") (pintype "passive"))
    )
    (net (code "67") (name "Net-(RN4C-2)") (class "Default")
      (node (ref "ON") (pin "A") (pinfunction "A_A") (pintype "passive"))
      (node (ref "RN4") (pin "5") (pinfunction "2_5") (pintype "passive"))
      (node (ref "RN4") (pin "6") (pinfunction "2_6") (pintype "passive"))
    )
    (net (code "68") (name "unconnected-(POWER-Pad1)") (class "Default")
      (node (ref "POWER") (pin "1") (pinfunction "1_1") (pintype "passive"))
    )
    (net (code "69") (name "unconnected-(RN3B-1-Pad2)") (class "Default")
      (node (ref "RN3") (pin "2") (pinfunction "1_2") (pintype "passive"))
    )
    (net (code "70") (name "unconnected-(RN3B-2-Pad7)") (class "Default")
      (node (ref "RN3") (pin "7") (pinfunction "2_7") (pintype "passive"))
    )
    (net (code "71") (name "unconnected-(RN3C-1-Pad3)") (class "Default")
      (node (ref "RN3") (pin "3") (pinfunction "1_3") (pintype "passive"))
    )
    (net (code "72") (name "unconnected-(RN3C-2-Pad6)") (class "Default")
      (node (ref "RN3") (pin "6") (pinfunction "2_6") (pintype "passive"))
    )
    (net (code "73") (name "unconnected-(U2-NC{slash}FB-Pad4)") (class "Default")
      (node (ref "U2") (pin "4") (pinfunction "NC/FB_4") (pintype "passive"))
    )
    (net (code "74") (name "unconnected-(U3-(AIN0{slash}INT1)PD1-Pad7)") (class "Default")
      (node (ref "U3") (pin "7") (pinfunction "(AIN0/INT1)PD1_7") (pintype "bidirectional"))
    )
    (net (code "75") (name "unconnected-(U3-(AIN2{slash}PCINT11)PC2-Pad5)") (class "Default")
      (node (ref "U3") (pin "5") (pinfunction "(AIN2/PCINT11)PC2_5") (pintype "bidirectional"))
    )
    (net (code "76") (name "unconnected-(U3-(INT4{slash}ICP1{slash}CLK0)PC7-Pad22)") (class "Default")
      (node (ref "U3") (pin "22") (pinfunction "(INT4/ICP1/CLK0)PC7_22") (pintype "bidirectional"))
    )
    (net (code "77") (name "unconnected-(U3-(OC0B{slash}INT0)PD0-Pad6)") (class "Default")
      (node (ref "U3") (pin "6") (pinfunction "(OC0B/INT0)PD0_6") (pintype "bidirectional"))
    )
    (net (code "78") (name "unconnected-(U3-(OC1A{slash}PCINT8)PC6-Pad23)") (class "Default")
      (node (ref "U3") (pin "23") (pinfunction "(OC1A/PCINT8)PC6_23") (pintype "bidirectional"))
    )
    (net (code "79") (name "unconnected-(U3-(PCINT9{slash}OC1B)PC5-Pad25)") (class "Default")
      (node (ref "U3") (pin "25") (pinfunction "(PCINT9/OC1B)PC5_25") (pintype "bidirectional"))
    )
    (net (code "80") (name "unconnected-(U3-(PCINT10)PC4-Pad26)") (class "Default")
      (node (ref "U3") (pin "26") (pinfunction "(PCINT10)PC4_26") (pintype "bidirectional"))
    )
    (net (code "81") (name "unconnected-(U3-(RTS{slash}AIN5{slash}INT6)PD6-Pad12)") (class "Default")
      (node (ref "U3") (pin "12") (pinfunction "(RTS/AIN5/INT6)PD6_12") (pintype "bidirectional"))
    )
    (net (code "82") (name "unconnected-(U3-(SS{slash}PCINT0)PB0-Pad14)") (class "Default")
      (node (ref "U3") (pin "14") (pinfunction "(SS/PCINT0)PB0_14") (pintype "bidirectional"))
    )
  )
)
